# swimate.net
KiCad netlist of a schematic drawn in EAGLE
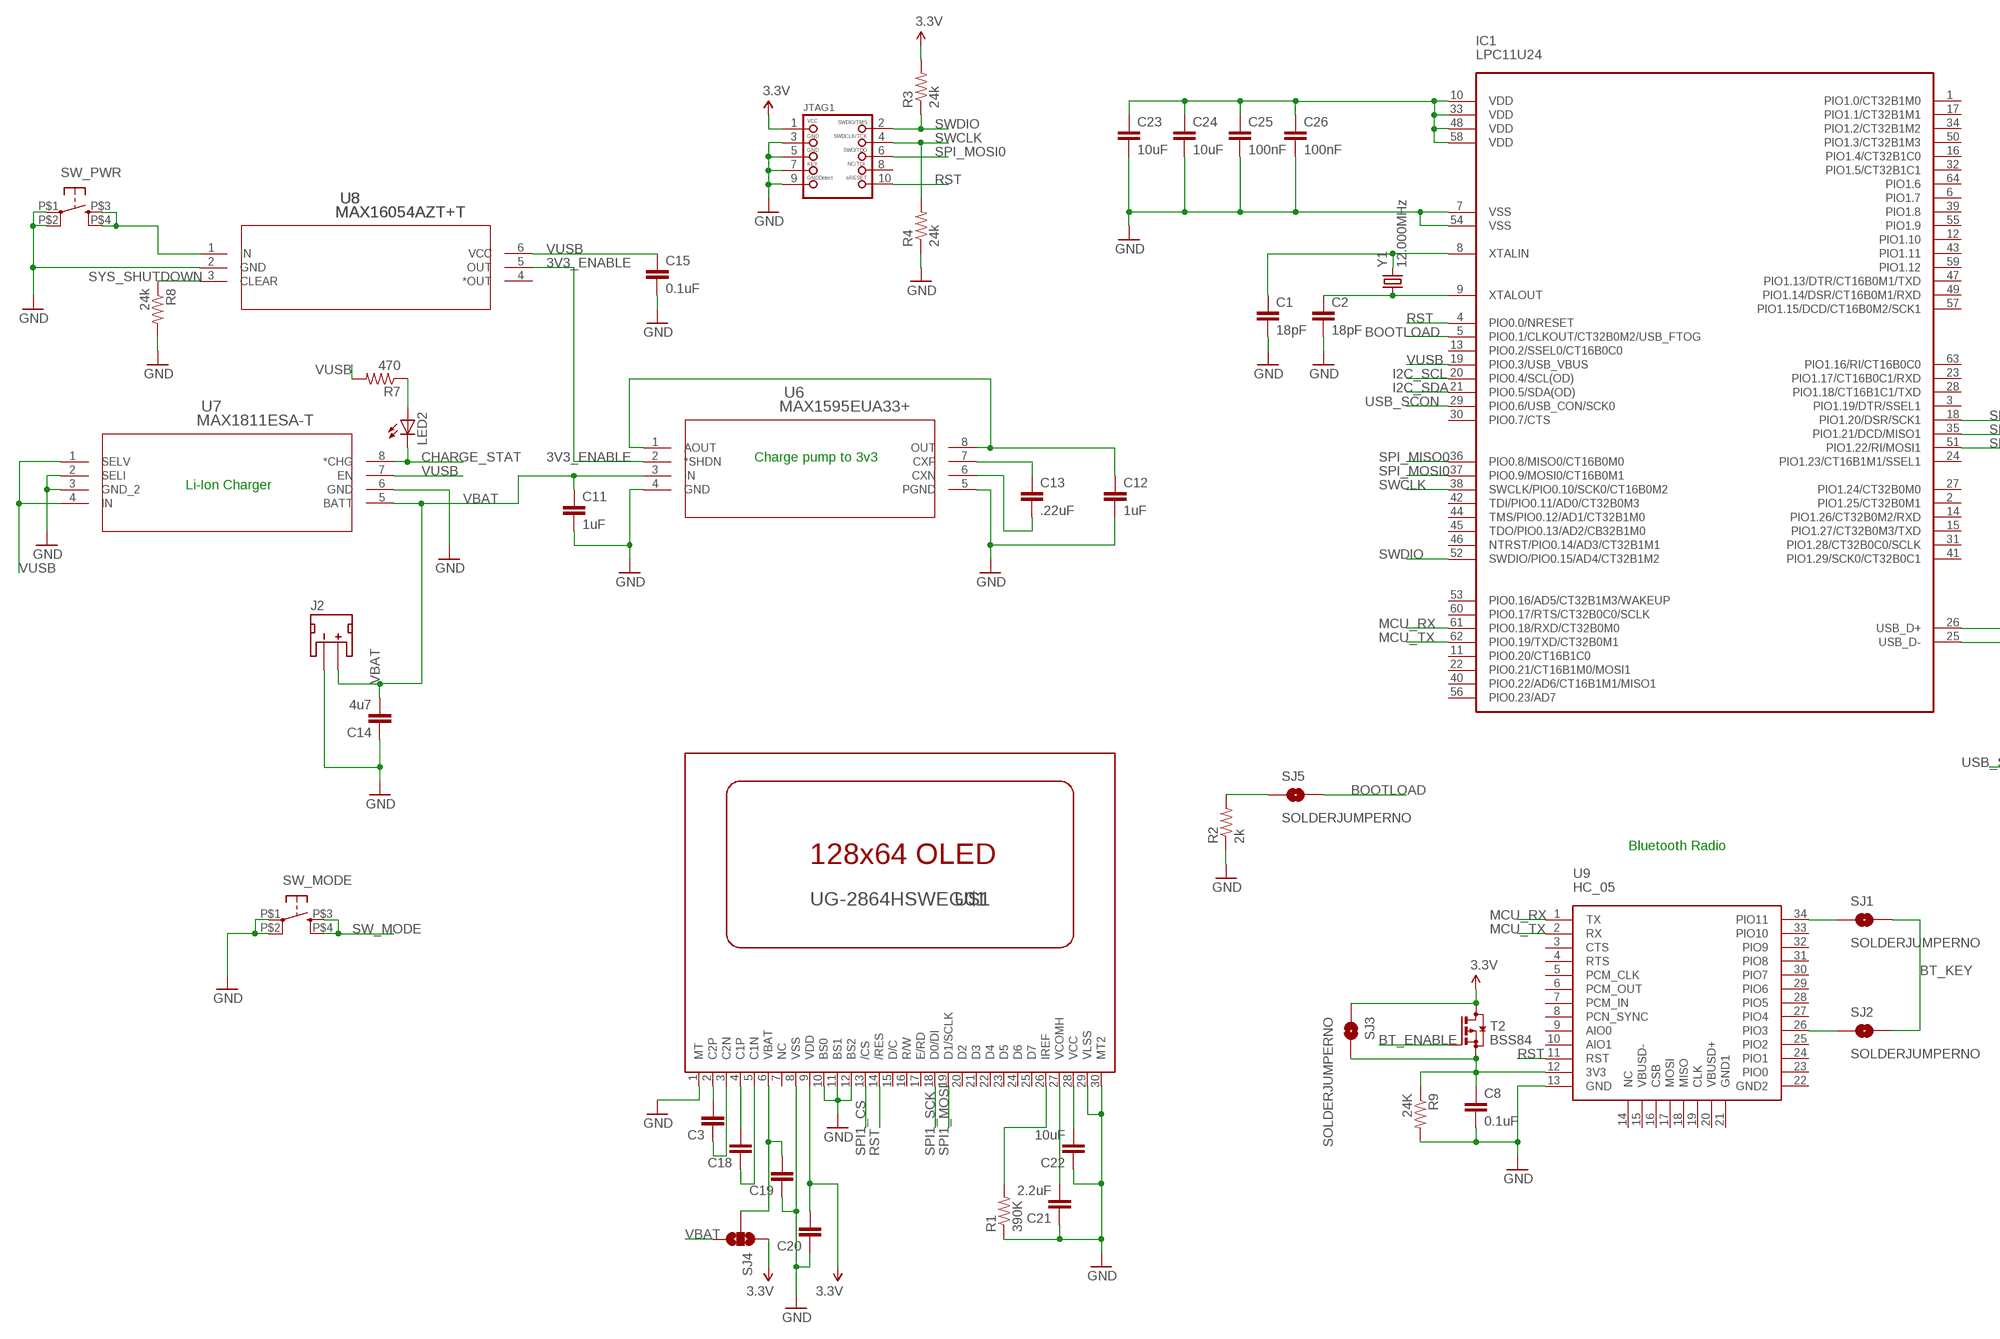
[diagram p0: schematic, sheet 1, part 1 of 2]
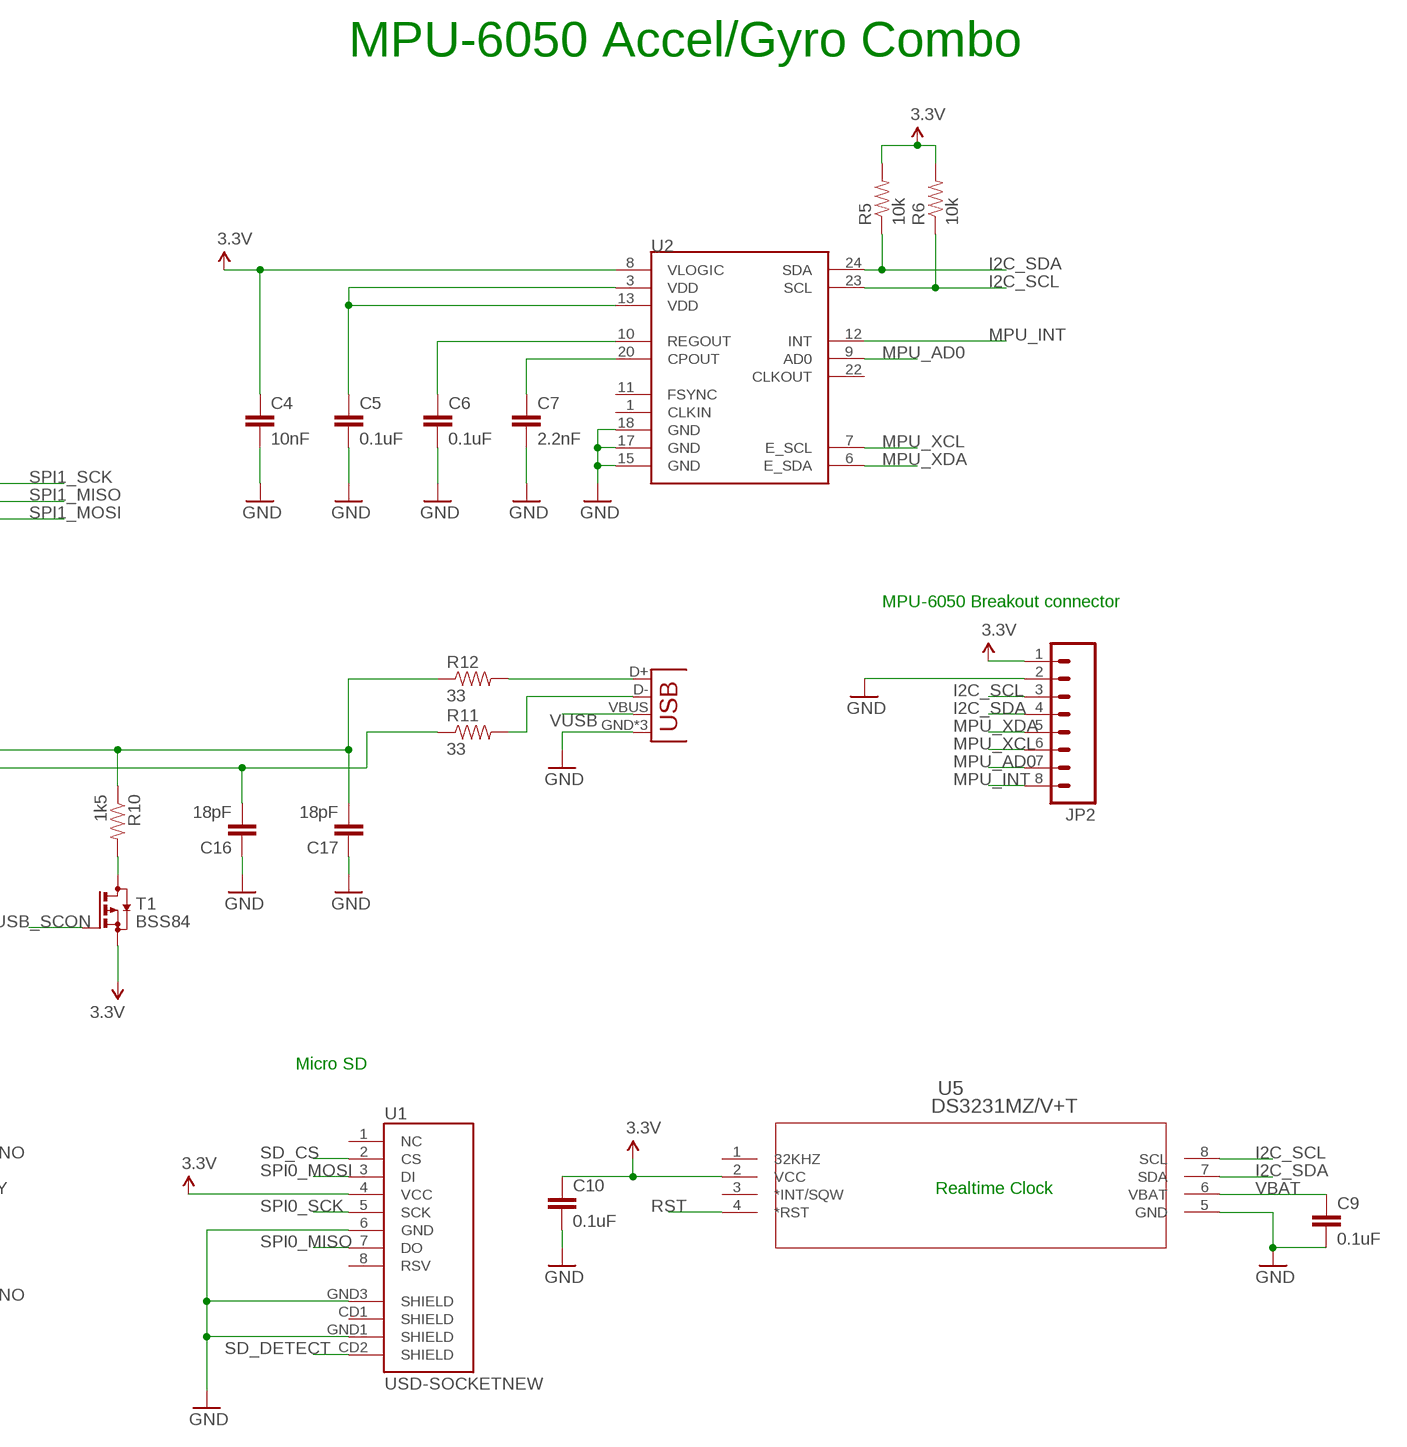
[diagram p1: schematic, sheet 1, part 2 of 2]

(export (version "E")
  (design (tool "Eeschema 10.0.6"))
  (components
    (comp (ref "C1")
      (value "18pF")
      (footprint "eagle-import:0805")
      (libsource (lib "eagle-import") (part "SparkFun-Passives_CAP0805"))
    )
    (comp (ref "C2")
      (value "18pF")
      (footprint "eagle-import:0805")
      (libsource (lib "eagle-import") (part "SparkFun-Passives_CAP0805"))
    )
    (comp (ref "C3")
      (value "CAP0805")
      (footprint "eagle-import:0805")
      (libsource (lib "eagle-import") (part "CAP0805"))
    )
    (comp (ref "C4")
      (value "10nF")
      (footprint "eagle-import:0805")
      (libsource (lib "eagle-import") (part "SparkFun-Passives_CAP0805"))
    )
    (comp (ref "C5")
      (value "0.1uF")
      (footprint "eagle-import:0805")
      (libsource (lib "eagle-import") (part "SparkFun-Passives_CAP0805"))
    )
    (comp (ref "C6")
      (value "0.1uF")
      (footprint "eagle-import:0805")
      (libsource (lib "eagle-import") (part "SparkFun-Passives_CAP0805"))
    )
    (comp (ref "C7")
      (value "2.2nF")
      (footprint "eagle-import:0805")
      (libsource (lib "eagle-import") (part "SparkFun-Passives_CAP0805"))
    )
    (comp (ref "C8")
      (value "0.1uF")
      (footprint "eagle-import:0805")
      (libsource (lib "eagle-import") (part "SparkFun-Passives_CAP0805"))
    )
    (comp (ref "C9")
      (value "0.1uF")
      (footprint "eagle-import:0805")
      (libsource (lib "eagle-import") (part "SparkFun-Passives_CAP0805"))
    )
    (comp (ref "C10")
      (value "0.1uF")
      (footprint "eagle-import:0805")
      (libsource (lib "eagle-import") (part "SparkFun-Passives_CAP0805"))
    )
    (comp (ref "C11")
      (value "1uF")
      (footprint "eagle-import:1206")
      (libsource (lib "eagle-import") (part "CAP1206"))
    )
    (comp (ref "C12")
      (value "1uF")
      (footprint "eagle-import:1206")
      (libsource (lib "eagle-import") (part "CAP1206"))
    )
    (comp (ref "C13")
      (value ".22uF")
      (footprint "eagle-import:0805")
      (libsource (lib "eagle-import") (part "SparkFun-Passives_CAP0805"))
    )
    (comp (ref "C14")
      (value "4u7")
      (footprint "eagle-import:1206")
      (libsource (lib "eagle-import") (part "SparkFun-Passives_CAP1206"))
    )
    (comp (ref "C15")
      (value "0.1uF")
      (footprint "eagle-import:0805")
      (libsource (lib "eagle-import") (part "SparkFun-Passives_CAP0805"))
    )
    (comp (ref "C16")
      (value "18pF")
      (footprint "eagle-import:0805")
      (libsource (lib "eagle-import") (part "SparkFun-Passives_CAP0805"))
    )
    (comp (ref "C17")
      (value "18pF")
      (footprint "eagle-import:0805")
      (libsource (lib "eagle-import") (part "SparkFun-Passives_CAP0805"))
    )
    (comp (ref "C18")
      (value "CAP0805")
      (footprint "eagle-import:0805")
      (libsource (lib "eagle-import") (part "CAP0805"))
    )
    (comp (ref "C19")
      (value "CAP0805")
      (footprint "eagle-import:0805")
      (libsource (lib "eagle-import") (part "CAP0805"))
    )
    (comp (ref "C20")
      (value "CAP0805")
      (footprint "eagle-import:0805")
      (libsource (lib "eagle-import") (part "CAP0805"))
    )
    (comp (ref "C21")
      (value "2.2uF")
      (footprint "eagle-import:0805")
      (libsource (lib "eagle-import") (part "CAP0805"))
    )
    (comp (ref "C22")
      (value "10uF")
      (footprint "eagle-import:0805")
      (libsource (lib "eagle-import") (part "CAP0805"))
    )
    (comp (ref "C23")
      (value "10uF")
      (footprint "eagle-import:0805")
      (libsource (lib "eagle-import") (part "CAP0805"))
    )
    (comp (ref "C24")
      (value "10uF")
      (footprint "eagle-import:0805")
      (libsource (lib "eagle-import") (part "CAP0805"))
    )
    (comp (ref "C25")
      (value "100nF")
      (footprint "eagle-import:0805")
      (libsource (lib "eagle-import") (part "CAP0805"))
    )
    (comp (ref "C26")
      (value "100nF")
      (footprint "eagle-import:0805")
      (libsource (lib "eagle-import") (part "CAP0805"))
    )
    (comp (ref "IC1")
      (value "LPC11U24")
      (footprint "eagle-import:MBED-ICS_LQFP64")
      (libsource (lib "eagle-import") (part "LPC11U24"))
    )
    (comp (ref "J2")
      (value "JST_2MM_MALE")
      (footprint "eagle-import:JST-2-SMD")
      (libsource (lib "eagle-import") (part "JST_2MM_MALE"))
    )
    (comp (ref "JP2")
      (value "M08")
      (footprint "eagle-import:1X08_PIN1_NO_SILK")
      (libsource (lib "eagle-import") (part "M08"))
    )
    (comp (ref "JP3")
      (value "USB-MICROB")
      (footprint "eagle-import:USB-MICROB")
      (libsource (lib "eagle-import") (part "USB-MICROB"))
    )
    (comp (ref "JTAG1")
      (value "JTAG-CORTEXM3")
      (footprint "eagle-import:2X05_1.27MM_SMT")
      (libsource (lib "eagle-import") (part "JTAG-CORTEXM3"))
    )
    (comp (ref "LED2")
      (value "LED1206")
      (footprint "eagle-import:LED-1206")
      (libsource (lib "eagle-import") (part "LED1206"))
    )
    (comp (ref "R1")
      (value "390K")
      (footprint "eagle-import:0805")
      (libsource (lib "eagle-import") (part "RESISTOR0805-RES"))
    )
    (comp (ref "R2")
      (value "2k")
      (footprint "eagle-import:0805")
      (libsource (lib "eagle-import") (part "RESISTOR0805-RES"))
    )
    (comp (ref "R3")
      (value "24k")
      (footprint "eagle-import:0805")
      (libsource (lib "eagle-import") (part "RESISTOR0805-RES"))
    )
    (comp (ref "R4")
      (value "24k")
      (footprint "eagle-import:0805")
      (libsource (lib "eagle-import") (part "RESISTOR0805-RES"))
    )
    (comp (ref "R5")
      (value "10k")
      (footprint "eagle-import:0805")
      (libsource (lib "eagle-import") (part "RESISTOR0805-RES"))
    )
    (comp (ref "R6")
      (value "10k")
      (footprint "eagle-import:0805")
      (libsource (lib "eagle-import") (part "RESISTOR0805-RES"))
    )
    (comp (ref "R7")
      (value "470")
      (footprint "eagle-import:0805")
      (libsource (lib "eagle-import") (part "RESISTOR0805-RES"))
    )
    (comp (ref "R8")
      (value "24k")
      (footprint "eagle-import:0805")
      (libsource (lib "eagle-import") (part "RESISTOR0805-RES"))
    )
    (comp (ref "R9")
      (value "24K")
      (footprint "eagle-import:0805")
      (libsource (lib "eagle-import") (part "RESISTOR0805-RES"))
    )
    (comp (ref "R10")
      (value "1k5")
      (footprint "eagle-import:0805")
      (libsource (lib "eagle-import") (part "RESISTOR0805-RES"))
    )
    (comp (ref "R11")
      (value "33")
      (footprint "eagle-import:0805")
      (libsource (lib "eagle-import") (part "RESISTOR0805-RES"))
    )
    (comp (ref "R12")
      (value "33")
      (footprint "eagle-import:0805")
      (libsource (lib "eagle-import") (part "RESISTOR0805-RES"))
    )
    (comp (ref "SJ1")
      (value "SOLDERJUMPERNO")
      (footprint "eagle-import:SJ_2S-NO")
      (libsource (lib "eagle-import") (part "SOLDERJUMPERNO"))
    )
    (comp (ref "SJ2")
      (value "SOLDERJUMPERNO")
      (footprint "eagle-import:SJ_2S-NO")
      (libsource (lib "eagle-import") (part "SOLDERJUMPERNO"))
    )
    (comp (ref "SJ3")
      (value "SOLDERJUMPERNO")
      (footprint "eagle-import:SJ_2S-NO")
      (libsource (lib "eagle-import") (part "SOLDERJUMPERNO"))
    )
    (comp (ref "SJ4")
      (value "SOLDERJUMPER_2WAYS")
      (footprint "eagle-import:SJ_3")
      (libsource (lib "eagle-import") (part "SOLDERJUMPER_2WAYS"))
    )
    (comp (ref "SJ5")
      (value "SOLDERJUMPERNO")
      (footprint "eagle-import:SJ_2S-NO")
      (libsource (lib "eagle-import") (part "SOLDERJUMPERNO"))
    )
    (comp (ref "SW_MODE")
      (value "TAC_SWITCHKSA_SEALED")
      (footprint "eagle-import:KSA_SEALED_TAC_SWITCH")
      (libsource (lib "eagle-import") (part "TAC_SWITCHKSA_SEALED"))
    )
    (comp (ref "SW_PWR")
      (value "TAC_SWITCHKSA_SEALED")
      (footprint "eagle-import:KSA_SEALED_TAC_SWITCH")
      (libsource (lib "eagle-import") (part "TAC_SWITCHKSA_SEALED"))
    )
    (comp (ref "T1")
      (value "BSS84")
      (footprint "eagle-import:SOT23")
      (libsource (lib "eagle-import") (part "BSS84"))
    )
    (comp (ref "T2")
      (value "BSS84")
      (footprint "eagle-import:SOT23")
      (libsource (lib "eagle-import") (part "BSS84"))
    )
    (comp (ref "U$1")
      (value "UG-2864HSWEG01")
      (footprint "eagle-import:1X30-0.7MM")
      (libsource (lib "eagle-import") (part "UG-2864HSWEG01"))
    )
    (comp (ref "U1")
      (value "USD-SOCKETNEW")
      (footprint "eagle-import:MICRO-SD-SOCKET-PP")
      (libsource (lib "eagle-import") (part "USD-SOCKETNEW"))
    )
    (comp (ref "U2")
      (value "MPU-9150QFN-24-NP")
      (footprint "eagle-import:QFN-24-NP")
      (libsource (lib "eagle-import") (part "MPU-9150QFN-24-NP"))
    )
    (comp (ref "U5")
      (value "DS3231MZ/V+T")
      (footprint "eagle-import:21-0041B_8")
      (libsource (lib "eagle-import") (part "DS3231MZ/V+T"))
    )
    (comp (ref "U6")
      (value "MAX1595EUA33+")
      (footprint "eagle-import:21-0036K")
      (libsource (lib "eagle-import") (part "MAX1595EUA33+"))
    )
    (comp (ref "U7")
      (value "MAX1811ESA-T")
      (footprint "eagle-import:21-0041B_8")
      (libsource (lib "eagle-import") (part "MAX1811ESA-T"))
    )
    (comp (ref "U8")
      (value "MAX16054AZT+T")
      (footprint "eagle-import:21-0114C")
      (libsource (lib "eagle-import") (part "MAX16054AZT+T"))
    )
    (comp (ref "U9")
      (value "HC_05")
      (footprint "eagle-import:BLUETOOTH_SMD")
      (libsource (lib "eagle-import") (part "HC_05"))
    )
    (comp (ref "Y1")
      (value "12.000MHz")
      (footprint "eagle-import:CRYSTAL-SMD-5X3")
      (libsource (lib "eagle-import") (part "CRYSTAL5X3"))
    )
  )
  (nets
    (net (code "1") (name "/3V3_ENABLE") (class "Default")
      (node (ref "U6") (pin "2") (pinfunction "*SHDN_2") (pintype "passive"))
      (node (ref "U8") (pin "5") (pinfunction "OUT_5") (pintype "output"))
    )
    (net (code "2") (name "/BOOTLOAD") (class "Default")
      (node (ref "IC1") (pin "5") (pinfunction "PIO0.1/CLKOUT/CT32B0M2/USB_FTOG_5") (pintype "bidirectional"))
      (node (ref "SJ5") (pin "2") (pinfunction "2_2") (pintype "passive"))
    )
    (net (code "3") (name "/BT_ENABLE") (class "Default")
      (node (ref "T2") (pin "1") (pinfunction "G_1") (pintype "passive"))
    )
    (net (code "4") (name "/BT_KEY") (class "Default")
      (node (ref "SJ1") (pin "2") (pinfunction "2_2") (pintype "passive"))
      (node (ref "SJ2") (pin "2") (pinfunction "2_2") (pintype "passive"))
    )
    (net (code "5") (name "/CHARGE_STAT") (class "Default")
      (node (ref "LED2") (pin "C") (pinfunction "C_C") (pintype "passive"))
      (node (ref "U7") (pin "8") (pinfunction "*CHG_8") (pintype "bidirectional"))
    )
    (net (code "6") (name "/I2C_SCL") (class "Default")
      (node (ref "IC1") (pin "20") (pinfunction "PIO0.4/SCL(OD)_20") (pintype "bidirectional"))
      (node (ref "JP2") (pin "3") (pinfunction "3_3") (pintype "passive"))
      (node (ref "R6") (pin "1") (pinfunction "1_1") (pintype "passive"))
      (node (ref "U2") (pin "23") (pinfunction "SCL_23") (pintype "bidirectional"))
      (node (ref "U5") (pin "8") (pinfunction "SCL_8") (pintype "passive"))
    )
    (net (code "7") (name "/I2C_SDA") (class "Default")
      (node (ref "IC1") (pin "21") (pinfunction "PIO0.5/SDA(OD)_21") (pintype "bidirectional"))
      (node (ref "JP2") (pin "4") (pinfunction "4_4") (pintype "passive"))
      (node (ref "R5") (pin "1") (pinfunction "1_1") (pintype "passive"))
      (node (ref "U2") (pin "24") (pinfunction "SDA_24") (pintype "bidirectional"))
      (node (ref "U5") (pin "7") (pinfunction "SDA_7") (pintype "passive"))
    )
    (net (code "8") (name "/MCU_RX") (class "Default")
      (node (ref "IC1") (pin "61") (pinfunction "PIO0.18/RXD/CT32B0M0_61") (pintype "bidirectional"))
      (node (ref "U9") (pin "1") (pinfunction "TX_1") (pintype "bidirectional"))
    )
    (net (code "9") (name "/MCU_TX") (class "Default")
      (node (ref "IC1") (pin "62") (pinfunction "PIO0.19/TXD/CT32B0M1_62") (pintype "bidirectional"))
      (node (ref "U9") (pin "2") (pinfunction "RX_2") (pintype "bidirectional"))
    )
    (net (code "10") (name "/MPU_AD0") (class "Default")
      (node (ref "JP2") (pin "7") (pinfunction "7_7") (pintype "passive"))
      (node (ref "U2") (pin "9") (pinfunction "AD0_9") (pintype "bidirectional"))
    )
    (net (code "11") (name "/MPU_INT") (class "Default")
      (node (ref "JP2") (pin "8") (pinfunction "8_8") (pintype "passive"))
      (node (ref "U2") (pin "12") (pinfunction "INT_12") (pintype "bidirectional"))
    )
    (net (code "12") (name "/MPU_XCL") (class "Default")
      (node (ref "JP2") (pin "6") (pinfunction "6_6") (pintype "passive"))
      (node (ref "U2") (pin "7") (pinfunction "E_SCL_7") (pintype "bidirectional"))
    )
    (net (code "13") (name "/MPU_XDA") (class "Default")
      (node (ref "JP2") (pin "5") (pinfunction "5_5") (pintype "passive"))
      (node (ref "U2") (pin "6") (pinfunction "E_SDA_6") (pintype "bidirectional"))
    )
    (net (code "14") (name "/RST") (class "Default")
      (node (ref "IC1") (pin "4") (pinfunction "PIO0.0/NRESET_4") (pintype "bidirectional"))
      (node (ref "JTAG1") (pin "10") (pinfunction "10_10") (pintype "passive"))
      (node (ref "U$1") (pin "14") (pinfunction "/RES_14") (pintype "input"))
      (node (ref "U5") (pin "4") (pinfunction "*RST_4") (pintype "passive"))
      (node (ref "U9") (pin "11") (pinfunction "RST_11") (pintype "bidirectional"))
    )
    (net (code "15") (name "/SD_CS") (class "Default")
      (node (ref "U1") (pin "2") (pinfunction "CS_2") (pintype "bidirectional"))
    )
    (net (code "16") (name "/SD_DETECT") (class "Default")
      (node (ref "U1") (pin "CD2") (pinfunction "SHIELD_CD2") (pintype "bidirectional"))
    )
    (net (code "17") (name "/SPI0_MISO") (class "Default")
      (node (ref "U1") (pin "7") (pinfunction "DO_7") (pintype "bidirectional"))
    )
    (net (code "18") (name "/SPI0_MOSI") (class "Default")
      (node (ref "U1") (pin "3") (pinfunction "DI_3") (pintype "bidirectional"))
    )
    (net (code "19") (name "/SPI0_SCK") (class "Default")
      (node (ref "U1") (pin "5") (pinfunction "SCK_5") (pintype "bidirectional"))
    )
    (net (code "20") (name "/SPI1_CS") (class "Default")
      (node (ref "U$1") (pin "13") (pinfunction "/CS_13") (pintype "input"))
    )
    (net (code "21") (name "/SPI1_MISO") (class "Default")
      (node (ref "IC1") (pin "35") (pinfunction "PIO1.21/DCD/MISO1_35") (pintype "bidirectional"))
    )
    (net (code "22") (name "/SPI1_MOSI") (class "Default")
      (node (ref "IC1") (pin "51") (pinfunction "PIO1.22/RI/MOSI1_51") (pintype "bidirectional"))
      (node (ref "U$1") (pin "19") (pinfunction "D1/SCLK_19") (pintype "bidirectional"))
    )
    (net (code "23") (name "/SPI1_SCK") (class "Default")
      (node (ref "IC1") (pin "18") (pinfunction "PIO1.20/DSR/SCK1_18") (pintype "bidirectional"))
      (node (ref "U$1") (pin "18") (pinfunction "D0/DI_18") (pintype "bidirectional"))
    )
    (net (code "24") (name "/SPI_MISO0") (class "Default")
      (node (ref "IC1") (pin "36") (pinfunction "PIO0.8/MISO0/CT16B0M0_36") (pintype "bidirectional"))
    )
    (net (code "25") (name "/SPI_MOSI0") (class "Default")
      (node (ref "IC1") (pin "37") (pinfunction "PIO0.9/MOSI0/CT16B0M1_37") (pintype "bidirectional"))
      (node (ref "JTAG1") (pin "6") (pinfunction "6_6") (pintype "passive"))
    )
    (net (code "26") (name "/SWCLK") (class "Default")
      (node (ref "IC1") (pin "38") (pinfunction "SWCLK/PIO0.10/SCK0/CT16B0M2_38") (pintype "bidirectional"))
      (node (ref "JTAG1") (pin "4") (pinfunction "4_4") (pintype "passive"))
      (node (ref "R4") (pin "2") (pinfunction "2_2") (pintype "passive"))
    )
    (net (code "27") (name "/SWDIO") (class "Default")
      (node (ref "IC1") (pin "52") (pinfunction "SWDIO/PIO0.15/AD4/CT32B1M2_52") (pintype "bidirectional"))
      (node (ref "JTAG1") (pin "2") (pinfunction "2_2") (pintype "passive"))
      (node (ref "R3") (pin "1") (pinfunction "1_1") (pintype "passive"))
    )
    (net (code "28") (name "/SW_MODE") (class "Default")
      (node (ref "SW_MODE") (pin "P$3") (pinfunction "3_P$3") (pintype "passive"))
      (node (ref "SW_MODE") (pin "P$4") (pinfunction "4_P$4") (pintype "passive"))
    )
    (net (code "29") (name "/SYS_SHUTDOWN") (class "Default")
      (node (ref "R8") (pin "1") (pinfunction "1_1") (pintype "passive"))
      (node (ref "U8") (pin "3") (pinfunction "CLEAR_3") (pintype "bidirectional"))
    )
    (net (code "30") (name "/USB_SCON") (class "Default")
      (node (ref "IC1") (pin "29") (pinfunction "PIO0.6/USB_CON/SCK0_29") (pintype "bidirectional"))
      (node (ref "T1") (pin "1") (pinfunction "G_1") (pintype "passive"))
    )
    (net (code "31") (name "/VBAT") (class "Default")
      (node (ref "C11") (pin "1") (pinfunction "1_1") (pintype "passive"))
      (node (ref "C14") (pin "2") (pinfunction "2_2") (pintype "passive"))
      (node (ref "C9") (pin "1") (pinfunction "1_1") (pintype "passive"))
      (node (ref "J2") (pin "2") (pinfunction "+_2") (pintype "bidirectional"))
      (node (ref "SJ4") (pin "3") (pinfunction "3_3") (pintype "passive"))
      (node (ref "U5") (pin "6") (pinfunction "VBAT_6") (pintype "power_in"))
      (node (ref "U6") (pin "3") (pinfunction "IN_3") (pintype "input"))
      (node (ref "U7") (pin "5") (pinfunction "BATT_5") (pintype "bidirectional"))
    )
    (net (code "32") (name "/VUSB") (class "Default")
      (node (ref "C15") (pin "1") (pinfunction "1_1") (pintype "passive"))
      (node (ref "IC1") (pin "19") (pinfunction "PIO0.3/USB_VBUS_19") (pintype "bidirectional"))
      (node (ref "JP3") (pin "VBUS") (pinfunction "VBUS_VBUS") (pintype "bidirectional"))
      (node (ref "R7") (pin "2") (pinfunction "2_2") (pintype "passive"))
      (node (ref "U7") (pin "1") (pinfunction "SELV_1") (pintype "bidirectional"))
      (node (ref "U7") (pin "4") (pinfunction "IN_4") (pintype "input"))
      (node (ref "U7") (pin "7") (pinfunction "EN_7") (pintype "bidirectional"))
      (node (ref "U8") (pin "6") (pinfunction "VCC_6") (pintype "power_in"))
    )
    (net (code "33") (name "3.3V") (class "Default")
      (node (ref "C10") (pin "1") (pinfunction "1_1") (pintype "passive"))
      (node (ref "C20") (pin "2") (pinfunction "2_2") (pintype "passive"))
      (node (ref "C4") (pin "1") (pinfunction "1_1") (pintype "passive"))
      (node (ref "JP2") (pin "1") (pinfunction "1_1") (pintype "passive"))
      (node (ref "JTAG1") (pin "1") (pinfunction "1_1") (pintype "passive"))
      (node (ref "R3") (pin "2") (pinfunction "2_2") (pintype "passive"))
      (node (ref "R5") (pin "2") (pinfunction "2_2") (pintype "passive"))
      (node (ref "R6") (pin "2") (pinfunction "2_2") (pintype "passive"))
      (node (ref "SJ3") (pin "1") (pinfunction "1_1") (pintype "passive"))
      (node (ref "SJ4") (pin "1") (pinfunction "1_1") (pintype "passive"))
      (node (ref "T1") (pin "2") (pinfunction "S_2") (pintype "passive"))
      (node (ref "T2") (pin "3") (pinfunction "D_3") (pintype "passive"))
      (node (ref "U$1") (pin "9") (pinfunction "VDD_9") (pintype "power_in"))
      (node (ref "U1") (pin "4") (pinfunction "VCC_4") (pintype "bidirectional"))
      (node (ref "U2") (pin "8") (pinfunction "VLOGIC_8") (pintype "bidirectional"))
      (node (ref "U5") (pin "2") (pinfunction "VCC_2") (pintype "power_in"))
    )
    (net (code "34") (name "GND") (class "Default")
      (node (ref "C1") (pin "2") (pinfunction "2_2") (pintype "passive"))
      (node (ref "C10") (pin "2") (pinfunction "2_2") (pintype "passive"))
      (node (ref "C11") (pin "2") (pinfunction "2_2") (pintype "passive"))
      (node (ref "C12") (pin "2") (pinfunction "2_2") (pintype "passive"))
      (node (ref "C14") (pin "1") (pinfunction "1_1") (pintype "passive"))
      (node (ref "C15") (pin "2") (pinfunction "2_2") (pintype "passive"))
      (node (ref "C16") (pin "1") (pinfunction "1_1") (pintype "passive"))
      (node (ref "C17") (pin "1") (pinfunction "1_1") (pintype "passive"))
      (node (ref "C19") (pin "1") (pinfunction "1_1") (pintype "passive"))
      (node (ref "C2") (pin "2") (pinfunction "2_2") (pintype "passive"))
      (node (ref "C20") (pin "1") (pinfunction "1_1") (pintype "passive"))
      (node (ref "C21") (pin "1") (pinfunction "1_1") (pintype "passive"))
      (node (ref "C22") (pin "1") (pinfunction "1_1") (pintype "passive"))
      (node (ref "C23") (pin "2") (pinfunction "2_2") (pintype "passive"))
      (node (ref "C24") (pin "2") (pinfunction "2_2") (pintype "passive"))
      (node (ref "C25") (pin "2") (pinfunction "2_2") (pintype "passive"))
      (node (ref "C26") (pin "2") (pinfunction "2_2") (pintype "passive"))
      (node (ref "C4") (pin "2") (pinfunction "2_2") (pintype "passive"))
      (node (ref "C5") (pin "2") (pinfunction "2_2") (pintype "passive"))
      (node (ref "C6") (pin "2") (pinfunction "2_2") (pintype "passive"))
      (node (ref "C7") (pin "2") (pinfunction "2_2") (pintype "passive"))
      (node (ref "C8") (pin "2") (pinfunction "2_2") (pintype "passive"))
      (node (ref "C9") (pin "2") (pinfunction "2_2") (pintype "passive"))
      (node (ref "IC1") (pin "54") (pinfunction "VSS_54") (pintype "bidirectional"))
      (node (ref "IC1") (pin "7") (pinfunction "VSS_7") (pintype "bidirectional"))
      (node (ref "J2") (pin "1") (pinfunction "-_1") (pintype "bidirectional"))
      (node (ref "JP2") (pin "2") (pinfunction "2_2") (pintype "passive"))
      (node (ref "JP3") (pin "GND") (pinfunction "GND_GND") (pintype "bidirectional"))
      (node (ref "JP3") (pin "MT1") (pinfunction "GND_MT1") (pintype "bidirectional"))
      (node (ref "JP3") (pin "MT2") (pinfunction "GND_MT2") (pintype "bidirectional"))
      (node (ref "JTAG1") (pin "3") (pinfunction "3_3") (pintype "passive"))
      (node (ref "JTAG1") (pin "5") (pinfunction "5_5") (pintype "passive"))
      (node (ref "JTAG1") (pin "7") (pinfunction "7_7") (pintype "passive"))
      (node (ref "JTAG1") (pin "9") (pinfunction "9_9") (pintype "passive"))
      (node (ref "R1") (pin "1") (pinfunction "1_1") (pintype "passive"))
      (node (ref "R2") (pin "1") (pinfunction "1_1") (pintype "passive"))
      (node (ref "R4") (pin "1") (pinfunction "1_1") (pintype "passive"))
      (node (ref "R8") (pin "2") (pinfunction "2_2") (pintype "passive"))
      (node (ref "R9") (pin "2") (pinfunction "2_2") (pintype "passive"))
      (node (ref "SW_MODE") (pin "P$1") (pinfunction "1_P$1") (pintype "passive"))
      (node (ref "SW_MODE") (pin "P$2") (pinfunction "2_P$2") (pintype "passive"))
      (node (ref "SW_PWR") (pin "P$1") (pinfunction "1_P$1") (pintype "passive"))
      (node (ref "SW_PWR") (pin "P$2") (pinfunction "2_P$2") (pintype "passive"))
      (node (ref "U$1") (pin "1") (pinfunction "MT_1") (pintype "input"))
      (node (ref "U$1") (pin "10") (pinfunction "BS0_10") (pintype "input"))
      (node (ref "U$1") (pin "11") (pinfunction "BS1_11") (pintype "input"))
      (node (ref "U$1") (pin "12") (pinfunction "BS2_12") (pintype "input"))
      (node (ref "U$1") (pin "29") (pinfunction "VLSS_29") (pintype "power_in"))
      (node (ref "U$1") (pin "30") (pinfunction "MT2_30") (pintype "input"))
      (node (ref "U$1") (pin "8") (pinfunction "VSS_8") (pintype "power_in"))
      (node (ref "U1") (pin "6") (pinfunction "GND_6") (pintype "bidirectional"))
      (node (ref "U1") (pin "GND1") (pinfunction "SHIELD_GND1") (pintype "bidirectional"))
      (node (ref "U1") (pin "GND3") (pinfunction "SHIELD_GND3") (pintype "bidirectional"))
      (node (ref "U2") (pin "15") (pinfunction "GND_15") (pintype "bidirectional"))
      (node (ref "U2") (pin "17") (pinfunction "GND_17") (pintype "bidirectional"))
      (node (ref "U2") (pin "18") (pinfunction "GND_18") (pintype "bidirectional"))
      (node (ref "U5") (pin "5") (pinfunction "GND_5") (pintype "power_in"))
      (node (ref "U6") (pin "4") (pinfunction "GND_4") (pintype "power_in"))
      (node (ref "U6") (pin "5") (pinfunction "PGND_5") (pintype "power_in"))
      (node (ref "U7") (pin "2") (pinfunction "SELI_2") (pintype "bidirectional"))
      (node (ref "U7") (pin "3") (pinfunction "GND_2_3") (pintype "power_in"))
      (node (ref "U7") (pin "6") (pinfunction "GND_6") (pintype "power_in"))
      (node (ref "U8") (pin "2") (pinfunction "GND_2") (pintype "power_in"))
      (node (ref "U9") (pin "13") (pinfunction "GND_13") (pintype "bidirectional"))
    )
    (net (code "35") (name "Net-(C5-Pad1)") (class "Default")
      (node (ref "C5") (pin "1") (pinfunction "1_1") (pintype "passive"))
      (node (ref "U2") (pin "13") (pinfunction "VDD_13") (pintype "bidirectional"))
      (node (ref "U2") (pin "3") (pinfunction "VDD_3") (pintype "bidirectional"))
    )
    (net (code "36") (name "Net-(C23-Pad1)") (class "Default")
      (node (ref "C23") (pin "1") (pinfunction "1_1") (pintype "passive"))
      (node (ref "C24") (pin "1") (pinfunction "1_1") (pintype "passive"))
      (node (ref "C25") (pin "1") (pinfunction "1_1") (pintype "passive"))
      (node (ref "C26") (pin "1") (pinfunction "1_1") (pintype "passive"))
      (node (ref "IC1") (pin "10") (pinfunction "VDD_10") (pintype "bidirectional"))
      (node (ref "IC1") (pin "33") (pinfunction "VDD_33") (pintype "bidirectional"))
      (node (ref "IC1") (pin "48") (pinfunction "VDD_48") (pintype "bidirectional"))
      (node (ref "IC1") (pin "58") (pinfunction "VDD_58") (pintype "bidirectional"))
    )
    (net (code "37") (name "Net-(IC1-USB_D+)") (class "Default")
      (node (ref "C17") (pin "2") (pinfunction "2_2") (pintype "passive"))
      (node (ref "IC1") (pin "26") (pinfunction "USB_D+_26") (pintype "bidirectional"))
      (node (ref "R10") (pin "1") (pinfunction "1_1") (pintype "passive"))
      (node (ref "R12") (pin "1") (pinfunction "1_1") (pintype "passive"))
    )
    (net (code "38") (name "Net-(IC1-USB_D-)") (class "Default")
      (node (ref "C16") (pin "2") (pinfunction "2_2") (pintype "passive"))
      (node (ref "IC1") (pin "25") (pinfunction "USB_D-_25") (pintype "bidirectional"))
      (node (ref "R11") (pin "1") (pinfunction "1_1") (pintype "passive"))
    )
    (net (code "39") (name "Net-(IC1-XTALIN)") (class "Default")
      (node (ref "C1") (pin "1") (pinfunction "1_1") (pintype "passive"))
      (node (ref "IC1") (pin "8") (pinfunction "XTALIN_8") (pintype "bidirectional"))
      (node (ref "Y1") (pin "3") (pinfunction "2_3") (pintype "passive"))
    )
    (net (code "40") (name "Net-(IC1-XTALOUT)") (class "Default")
      (node (ref "C2") (pin "1") (pinfunction "1_1") (pintype "passive"))
      (node (ref "IC1") (pin "9") (pinfunction "XTALOUT_9") (pintype "bidirectional"))
      (node (ref "Y1") (pin "1") (pinfunction "1_1") (pintype "passive"))
    )
    (net (code "41") (name "Net-(JP3-PadD+)") (class "Default")
      (node (ref "JP3") (pin "D+") (pinfunction "D+_D+") (pintype "bidirectional"))
      (node (ref "R12") (pin "2") (pinfunction "2_2") (pintype "passive"))
    )
    (net (code "42") (name "Net-(JP3-PadD-)") (class "Default")
      (node (ref "JP3") (pin "D-") (pinfunction "D-_D-") (pintype "bidirectional"))
      (node (ref "R11") (pin "2") (pinfunction "2_2") (pintype "passive"))
    )
    (net (code "43") (name "Net-(LED2-PadA)") (class "Default")
      (node (ref "LED2") (pin "A") (pinfunction "A_A") (pintype "passive"))
      (node (ref "R7") (pin "1") (pinfunction "1_1") (pintype "passive"))
    )
    (net (code "44") (name "Net-(R2-Pad2)") (class "Default")
      (node (ref "R2") (pin "2") (pinfunction "2_2") (pintype "passive"))
      (node (ref "SJ5") (pin "1") (pinfunction "1_1") (pintype "passive"))
    )
    (net (code "45") (name "Net-(SW_PWR-3)") (class "Default")
      (node (ref "SW_PWR") (pin "P$3") (pinfunction "3_P$3") (pintype "passive"))
      (node (ref "SW_PWR") (pin "P$4") (pinfunction "4_P$4") (pintype "passive"))
      (node (ref "U8") (pin "1") (pinfunction "IN_1") (pintype "input"))
    )
    (net (code "46") (name "Net-(T1-D)") (class "Default")
      (node (ref "R10") (pin "2") (pinfunction "2_2") (pintype "passive"))
      (node (ref "T1") (pin "3") (pinfunction "D_3") (pintype "passive"))
    )
    (net (code "47") (name "Net-(T2-S)") (class "Default")
      (node (ref "C8") (pin "1") (pinfunction "1_1") (pintype "passive"))
      (node (ref "R9") (pin "1") (pinfunction "1_1") (pintype "passive"))
      (node (ref "SJ3") (pin "2") (pinfunction "2_2") (pintype "passive"))
      (node (ref "T2") (pin "2") (pinfunction "S_2") (pintype "passive"))
      (node (ref "U9") (pin "12") (pinfunction "3V3_12") (pintype "bidirectional"))
    )
    (net (code "48") (name "Net-(U$1-C1N)") (class "Default")
      (node (ref "C18") (pin "1") (pinfunction "1_1") (pintype "passive"))
      (node (ref "U$1") (pin "5") (pinfunction "C1N_5") (pintype "input"))
    )
    (net (code "49") (name "Net-(U$1-C1P)") (class "Default")
      (node (ref "C18") (pin "2") (pinfunction "2_2") (pintype "passive"))
      (node (ref "U$1") (pin "4") (pinfunction "C1P_4") (pintype "input"))
    )
    (net (code "50") (name "Net-(U$1-C2N)") (class "Default")
      (node (ref "C3") (pin "1") (pinfunction "1_1") (pintype "passive"))
      (node (ref "U$1") (pin "3") (pinfunction "C2N_3") (pintype "input"))
    )
    (net (code "51") (name "Net-(U$1-C2P)") (class "Default")
      (node (ref "C3") (pin "2") (pinfunction "2_2") (pintype "passive"))
      (node (ref "U$1") (pin "2") (pinfunction "C2P_2") (pintype "input"))
    )
    (net (code "52") (name "Net-(U$1-IREF)") (class "Default")
      (node (ref "R1") (pin "2") (pinfunction "2_2") (pintype "passive"))
      (node (ref "U$1") (pin "26") (pinfunction "IREF_26") (pintype "input"))
    )
    (net (code "53") (name "Net-(U$1-VBAT)") (class "Default")
      (node (ref "C19") (pin "2") (pinfunction "2_2") (pintype "passive"))
      (node (ref "SJ4") (pin "2") (pinfunction "2_2") (pintype "passive"))
      (node (ref "U$1") (pin "6") (pinfunction "VBAT_6") (pintype "input"))
    )
    (net (code "54") (name "Net-(U$1-VCC)") (class "Default")
      (node (ref "C22") (pin "2") (pinfunction "2_2") (pintype "passive"))
      (node (ref "U$1") (pin "28") (pinfunction "VCC_28") (pintype "power_in"))
    )
    (net (code "55") (name "Net-(U$1-VCOMH)") (class "Default")
      (node (ref "C21") (pin "2") (pinfunction "2_2") (pintype "passive"))
      (node (ref "U$1") (pin "27") (pinfunction "VCOMH_27") (pintype "output"))
    )
    (net (code "56") (name "Net-(U2-CPOUT)") (class "Default")
      (node (ref "C7") (pin "1") (pinfunction "1_1") (pintype "passive"))
      (node (ref "U2") (pin "20") (pinfunction "CPOUT_20") (pintype "bidirectional"))
    )
    (net (code "57") (name "Net-(U2-REGOUT)") (class "Default")
      (node (ref "C6") (pin "1") (pinfunction "1_1") (pintype "passive"))
      (node (ref "U2") (pin "10") (pinfunction "REGOUT_10") (pintype "bidirectional"))
    )
    (net (code "58") (name "Net-(U6-AOUT)") (class "Default")
      (node (ref "C12") (pin "1") (pinfunction "1_1") (pintype "passive"))
      (node (ref "U6") (pin "1") (pinfunction "AOUT_1") (pintype "output"))
      (node (ref "U6") (pin "8") (pinfunction "OUT_8") (pintype "output"))
    )
    (net (code "59") (name "Net-(U6-CXN)") (class "Default")
      (node (ref "C13") (pin "2") (pinfunction "2_2") (pintype "passive"))
      (node (ref "U6") (pin "6") (pinfunction "CXN_6") (pintype "passive"))
    )
    (net (code "60") (name "Net-(U6-CXP)") (class "Default")
      (node (ref "C13") (pin "1") (pinfunction "1_1") (pintype "passive"))
      (node (ref "U6") (pin "7") (pinfunction "CXP_7") (pintype "passive"))
    )
    (net (code "61") (name "Net-(U9-PIO3)") (class "Default")
      (node (ref "SJ2") (pin "1") (pinfunction "1_1") (pintype "passive"))
      (node (ref "U9") (pin "26") (pinfunction "PIO3_26") (pintype "bidirectional"))
    )
    (net (code "62") (name "Net-(U9-PIO11)") (class "Default")
      (node (ref "SJ1") (pin "1") (pinfunction "1_1") (pintype "passive"))
      (node (ref "U9") (pin "34") (pinfunction "PIO11_34") (pintype "bidirectional"))
    )
    (net (code "63") (name "unconnected-(IC1-NTRST{slash}PIO0.14{slash}AD3{slash}CT32B1M1-Pad46)") (class "Default")
      (node (ref "IC1") (pin "46") (pinfunction "NTRST/PIO0.14/AD3/CT32B1M1_46") (pintype "bidirectional"))
    )
    (net (code "64") (name "unconnected-(IC1-PIO0.2{slash}SSEL0{slash}CT16B0C0-Pad13)") (class "Default")
      (node (ref "IC1") (pin "13") (pinfunction "PIO0.2/SSEL0/CT16B0C0_13") (pintype "bidirectional"))
    )
    (net (code "65") (name "unconnected-(IC1-PIO0.7{slash}CTS-Pad30)") (class "Default")
      (node (ref "IC1") (pin "30") (pinfunction "PIO0.7/CTS_30") (pintype "bidirectional"))
    )
    (net (code "66") (name "unconnected-(IC1-PIO0.16{slash}AD5{slash}CT32B1M3{slash}WAKEUP-Pad53)") (class "Default")
      (node (ref "IC1") (pin "53") (pinfunction "PIO0.16/AD5/CT32B1M3/WAKEUP_53") (pintype "bidirectional"))
    )
    (net (code "67") (name "unconnected-(IC1-PIO0.17{slash}RTS{slash}CT32B0C0{slash}SCLK-Pad60)") (class "Default")
      (node (ref "IC1") (pin "60") (pinfunction "PIO0.17/RTS/CT32B0C0/SCLK_60") (pintype "bidirectional"))
    )
    (net (code "68") (name "unconnected-(IC1-PIO0.20{slash}CT16B1C0-Pad11)") (class "Default")
      (node (ref "IC1") (pin "11") (pinfunction "PIO0.20/CT16B1C0_11") (pintype "bidirectional"))
    )
    (net (code "69") (name "unconnected-(IC1-PIO0.21{slash}CT16B1M0{slash}MOSI1-Pad22)") (class "Default")
      (node (ref "IC1") (pin "22") (pinfunction "PIO0.21/CT16B1M0/MOSI1_22") (pintype "bidirectional"))
    )
    (net (code "70") (name "unconnected-(IC1-PIO0.22{slash}AD6{slash}CT16B1M1{slash}MISO1-Pad40)") (class "Default")
      (node (ref "IC1") (pin "40") (pinfunction "PIO0.22/AD6/CT16B1M1/MISO1_40") (pintype "bidirectional"))
    )
    (net (code "71") (name "unconnected-(IC1-PIO0.23{slash}AD7-Pad56)") (class "Default")
      (node (ref "IC1") (pin "56") (pinfunction "PIO0.23/AD7_56") (pintype "bidirectional"))
    )
    (net (code "72") (name "unconnected-(IC1-PIO1.0{slash}CT32B1M0-Pad1)") (class "Default")
      (node (ref "IC1") (pin "1") (pinfunction "PIO1.0/CT32B1M0_1") (pintype "bidirectional"))
    )
    (net (code "73") (name "unconnected-(IC1-PIO1.1{slash}CT32B1M1-Pad17)") (class "Default")
      (node (ref "IC1") (pin "17") (pinfunction "PIO1.1/CT32B1M1_17") (pintype "bidirectional"))
    )
    (net (code "74") (name "unconnected-(IC1-PIO1.2{slash}CT32B1M2-Pad34)") (class "Default")
      (node (ref "IC1") (pin "34") (pinfunction "PIO1.2/CT32B1M2_34") (pintype "bidirectional"))
    )
    (net (code "75") (name "unconnected-(IC1-PIO1.3{slash}CT32B1M3-Pad50)") (class "Default")
      (node (ref "IC1") (pin "50") (pinfunction "PIO1.3/CT32B1M3_50") (pintype "bidirectional"))
    )
    (net (code "76") (name "unconnected-(IC1-PIO1.4{slash}CT32B1C0-Pad16)") (class "Default")
      (node (ref "IC1") (pin "16") (pinfunction "PIO1.4/CT32B1C0_16") (pintype "bidirectional"))
    )
    (net (code "77") (name "unconnected-(IC1-PIO1.5{slash}CT32B1C1-Pad32)") (class "Default")
      (node (ref "IC1") (pin "32") (pinfunction "PIO1.5/CT32B1C1_32") (pintype "bidirectional"))
    )
    (net (code "78") (name "unconnected-(IC1-PIO1.6-Pad64)") (class "Default")
      (node (ref "IC1") (pin "64") (pinfunction "PIO1.6_64") (pintype "bidirectional"))
    )
    (net (code "79") (name "unconnected-(IC1-PIO1.7-Pad6)") (class "Default")
      (node (ref "IC1") (pin "6") (pinfunction "PIO1.7_6") (pintype "bidirectional"))
    )
    (net (code "80") (name "unconnected-(IC1-PIO1.8-Pad39)") (class "Default")
      (node (ref "IC1") (pin "39") (pinfunction "PIO1.8_39") (pintype "bidirectional"))
    )
    (net (code "81") (name "unconnected-(IC1-PIO1.9-Pad55)") (class "Default")
      (node (ref "IC1") (pin "55") (pinfunction "PIO1.9_55") (pintype "bidirectional"))
    )
    (net (code "82") (name "unconnected-(IC1-PIO1.10-Pad12)") (class "Default")
      (node (ref "IC1") (pin "12") (pinfunction "PIO1.10_12") (pintype "bidirectional"))
    )
    (net (code "83") (name "unconnected-(IC1-PIO1.11-Pad43)") (class "Default")
      (node (ref "IC1") (pin "43") (pinfunction "PIO1.11_43") (pintype "bidirectional"))
    )
    (net (code "84") (name "unconnected-(IC1-PIO1.12-Pad59)") (class "Default")
      (node (ref "IC1") (pin "59") (pinfunction "PIO1.12_59") (pintype "bidirectional"))
    )
    (net (code "85") (name "unconnected-(IC1-PIO1.13{slash}DTR{slash}CT16B0M1{slash}TXD-Pad47)") (class "Default")
      (node (ref "IC1") (pin "47") (pinfunction "PIO1.13/DTR/CT16B0M1/TXD_47") (pintype "bidirectional"))
    )
    (net (code "86") (name "unconnected-(IC1-PIO1.14{slash}DSR{slash}CT16B0M1{slash}RXD-Pad49)") (class "Default")
      (node (ref "IC1") (pin "49") (pinfunction "PIO1.14/DSR/CT16B0M1/RXD_49") (pintype "bidirectional"))
    )
    (net (code "87") (name "unconnected-(IC1-PIO1.15{slash}DCD{slash}CT16B0M2{slash}SCK1-Pad57)") (class "Default")
      (node (ref "IC1") (pin "57") (pinfunction "PIO1.15/DCD/CT16B0M2/SCK1_57") (pintype "bidirectional"))
    )
    (net (code "88") (name "unconnected-(IC1-PIO1.16{slash}RI{slash}CT16B0C0-Pad63)") (class "Default")
      (node (ref "IC1") (pin "63") (pinfunction "PIO1.16/RI/CT16B0C0_63") (pintype "bidirectional"))
    )
    (net (code "89") (name "unconnected-(IC1-PIO1.17{slash}CT16B0C1{slash}RXD-Pad23)") (class "Default")
      (node (ref "IC1") (pin "23") (pinfunction "PIO1.17/CT16B0C1/RXD_23") (pintype "bidirectional"))
    )
    (net (code "90") (name "unconnected-(IC1-PIO1.18{slash}CT16B1C1{slash}TXD-Pad28)") (class "Default")
      (node (ref "IC1") (pin "28") (pinfunction "PIO1.18/CT16B1C1/TXD_28") (pintype "bidirectional"))
    )
    (net (code "91") (name "unconnected-(IC1-PIO1.19{slash}DTR{slash}SSEL1-Pad3)") (class "Default")
      (node (ref "IC1") (pin "3") (pinfunction "PIO1.19/DTR/SSEL1_3") (pintype "bidirectional"))
    )
    (net (code "92") (name "unconnected-(IC1-PIO1.23{slash}CT16B1M1{slash}SSEL1-Pad24)") (class "Default")
      (node (ref "IC1") (pin "24") (pinfunction "PIO1.23/CT16B1M1/SSEL1_24") (pintype "bidirectional"))
    )
    (net (code "93") (name "unconnected-(IC1-PIO1.24{slash}CT32B0M0-Pad27)") (class "Default")
      (node (ref "IC1") (pin "27") (pinfunction "PIO1.24/CT32B0M0_27") (pintype "bidirectional"))
    )
    (net (code "94") (name "unconnected-(IC1-PIO1.25{slash}CT32B0M1-Pad2)") (class "Default")
      (node (ref "IC1") (pin "2") (pinfunction "PIO1.25/CT32B0M1_2") (pintype "bidirectional"))
    )
    (net (code "95") (name "unconnected-(IC1-PIO1.26{slash}CT32B0M2{slash}RXD-Pad14)") (class "Default")
      (node (ref "IC1") (pin "14") (pinfunction "PIO1.26/CT32B0M2/RXD_14") (pintype "bidirectional"))
    )
    (net (code "96") (name "unconnected-(IC1-PIO1.27{slash}CT32B0M3{slash}TXD-Pad15)") (class "Default")
      (node (ref "IC1") (pin "15") (pinfunction "PIO1.27/CT32B0M3/TXD_15") (pintype "bidirectional"))
    )
    (net (code "97") (name "unconnected-(IC1-PIO1.28{slash}CT32B0C0{slash}SCLK-Pad31)") (class "Default")
      (node (ref "IC1") (pin "31") (pinfunction "PIO1.28/CT32B0C0/SCLK_31") (pintype "bidirectional"))
    )
    (net (code "98") (name "unconnected-(IC1-PIO1.29{slash}SCK0{slash}CT32B0C1-Pad41)") (class "Default")
      (node (ref "IC1") (pin "41") (pinfunction "PIO1.29/SCK0/CT32B0C1_41") (pintype "bidirectional"))
    )
    (net (code "99") (name "unconnected-(IC1-TDI{slash}PIO0.11{slash}AD0{slash}CT32B0M3-Pad42)") (class "Default")
      (node (ref "IC1") (pin "42") (pinfunction "TDI/PIO0.11/AD0/CT32B0M3_42") (pintype "bidirectional"))
    )
    (net (code "100") (name "unconnected-(IC1-TDO{slash}PIO0.13{slash}AD2{slash}CB32B1M0-Pad45)") (class "Default")
      (node (ref "IC1") (pin "45") (pinfunction "TDO/PIO0.13/AD2/CB32B1M0_45") (pintype "bidirectional"))
    )
    (net (code "101") (name "unconnected-(IC1-TMS{slash}PIO0.12{slash}AD1{slash}CT32B1M0-Pad44)") (class "Default")
      (node (ref "IC1") (pin "44") (pinfunction "TMS/PIO0.12/AD1/CT32B1M0_44") (pintype "bidirectional"))
    )
    (net (code "102") (name "unconnected-(J2-PAD1-PadNC1)") (class "Default")
      (node (ref "J2") (pin "NC1") (pinfunction "PAD1_NC1") (pintype "bidirectional"))
    )
    (net (code "103") (name "unconnected-(J2-PAD2-PadNC2)") (class "Default")
      (node (ref "J2") (pin "NC2") (pinfunction "PAD2_NC2") (pintype "bidirectional"))
    )
    (net (code "104") (name "unconnected-(JTAG1-Pad8)") (class "Default")
      (node (ref "JTAG1") (pin "8") (pinfunction "8_8") (pintype "passive"))
    )
    (net (code "105") (name "unconnected-(U$1-D2-Pad20)") (class "Default")
      (node (ref "U$1") (pin "20") (pinfunction "D2_20") (pintype "bidirectional"))
    )
    (net (code "106") (name "unconnected-(U$1-D3-Pad21)") (class "Default")
      (node (ref "U$1") (pin "21") (pinfunction "D3_21") (pintype "bidirectional"))
    )
    (net (code "107") (name "unconnected-(U$1-D4-Pad22)") (class "Default")
      (node (ref "U$1") (pin "22") (pinfunction "D4_22") (pintype "bidirectional"))
    )
    (net (code "108") (name "unconnected-(U$1-D5-Pad23)") (class "Default")
      (node (ref "U$1") (pin "23") (pinfunction "D5_23") (pintype "bidirectional"))
    )
    (net (code "109") (name "unconnected-(U$1-D6-Pad24)") (class "Default")
      (node (ref "U$1") (pin "24") (pinfunction "D6_24") (pintype "bidirectional"))
    )
    (net (code "110") (name "unconnected-(U$1-D7-Pad25)") (class "Default")
      (node (ref "U$1") (pin "25") (pinfunction "D7_25") (pintype "bidirectional"))
    )
    (net (code "111") (name "unconnected-(U$1-D{slash}C-Pad15)") (class "Default")
      (node (ref "U$1") (pin "15") (pinfunction "D/C_15") (pintype "input"))
    )
    (net (code "112") (name "unconnected-(U$1-E{slash}RD-Pad17)") (class "Default")
      (node (ref "U$1") (pin "17") (pinfunction "E/RD_17") (pintype "input"))
    )
    (net (code "113") (name "unconnected-(U$1-NC-Pad7)") (class "Default")
      (node (ref "U$1") (pin "7") (pinfunction "NC_7") (pintype "no_connect"))
    )
    (net (code "114") (name "unconnected-(U$1-R{slash}W-Pad16)") (class "Default")
      (node (ref "U$1") (pin "16") (pinfunction "R/W_16") (pintype "input"))
    )
    (net (code "115") (name "unconnected-(U1-NC-Pad1)") (class "Default")
      (node (ref "U1") (pin "1") (pinfunction "NC_1") (pintype "bidirectional"))
    )
    (net (code "116") (name "unconnected-(U1-RSV-Pad8)") (class "Default")
      (node (ref "U1") (pin "8") (pinfunction "RSV_8") (pintype "bidirectional"))
    )
    (net (code "117") (name "unconnected-(U1-SHIELD-PadCD1)") (class "Default")
      (node (ref "U1") (pin "CD1") (pinfunction "SHIELD_CD1") (pintype "bidirectional"))
    )
    (net (code "118") (name "unconnected-(U2-CLKIN-Pad1)") (class "Default")
      (node (ref "U2") (pin "1") (pinfunction "CLKIN_1") (pintype "bidirectional"))
    )
    (net (code "119") (name "unconnected-(U2-CLKOUT-Pad22)") (class "Default")
      (node (ref "U2") (pin "22") (pinfunction "CLKOUT_22") (pintype "bidirectional"))
    )
    (net (code "120") (name "unconnected-(U2-FSYNC-Pad11)") (class "Default")
      (node (ref "U2") (pin "11") (pinfunction "FSYNC_11") (pintype "bidirectional"))
    )
    (net (code "121") (name "unconnected-(U5-*INT{slash}SQW-Pad3)") (class "Default")
      (node (ref "U5") (pin "3") (pinfunction "*INT/SQW_3") (pintype "passive"))
    )
    (net (code "122") (name "unconnected-(U5-32KHZ-Pad1)") (class "Default")
      (node (ref "U5") (pin "1") (pinfunction "32KHZ_1") (pintype "passive"))
    )
    (net (code "123") (name "unconnected-(U8-*OUT-Pad4)") (class "Default")
      (node (ref "U8") (pin "4") (pinfunction "*OUT_4") (pintype "output"))
    )
    (net (code "124") (name "unconnected-(U9-AIO0-Pad9)") (class "Default")
      (node (ref "U9") (pin "9") (pinfunction "AIO0_9") (pintype "bidirectional"))
    )
    (net (code "125") (name "unconnected-(U9-AIO1-Pad10)") (class "Default")
      (node (ref "U9") (pin "10") (pinfunction "AIO1_10") (pintype "bidirectional"))
    )
    (net (code "126") (name "unconnected-(U9-CLK-Pad19)") (class "Default")
      (node (ref "U9") (pin "19") (pinfunction "CLK_19") (pintype "bidirectional"))
    )
    (net (code "127") (name "unconnected-(U9-CSB-Pad16)") (class "Default")
      (node (ref "U9") (pin "16") (pinfunction "CSB_16") (pintype "bidirectional"))
    )
    (net (code "128") (name "unconnected-(U9-CTS-Pad3)") (class "Default")
      (node (ref "U9") (pin "3") (pinfunction "CTS_3") (pintype "bidirectional"))
    )
    (net (code "129") (name "unconnected-(U9-GND1-Pad21)") (class "Default")
      (node (ref "U9") (pin "21") (pinfunction "GND1_21") (pintype "bidirectional"))
    )
    (net (code "130") (name "unconnected-(U9-GND2-Pad22)") (class "Default")
      (node (ref "U9") (pin "22") (pinfunction "GND2_22") (pintype "bidirectional"))
    )
    (net (code "131") (name "unconnected-(U9-MISO-Pad18)") (class "Default")
      (node (ref "U9") (pin "18") (pinfunction "MISO_18") (pintype "bidirectional"))
    )
    (net (code "132") (name "unconnected-(U9-MOSI-Pad17)") (class "Default")
      (node (ref "U9") (pin "17") (pinfunction "MOSI_17") (pintype "bidirectional"))
    )
    (net (code "133") (name "unconnected-(U9-NC-Pad14)") (class "Default")
      (node (ref "U9") (pin "14") (pinfunction "NC_14") (pintype "bidirectional"))
    )
    (net (code "134") (name "unconnected-(U9-PCM_CLK-Pad5)") (class "Default")
      (node (ref "U9") (pin "5") (pinfunction "PCM_CLK_5") (pintype "bidirectional"))
    )
    (net (code "135") (name "unconnected-(U9-PCM_IN-Pad7)") (class "Default")
      (node (ref "U9") (pin "7") (pinfunction "PCM_IN_7") (pintype "bidirectional"))
    )
    (net (code "136") (name "unconnected-(U9-PCM_OUT-Pad6)") (class "Default")
      (node (ref "U9") (pin "6") (pinfunction "PCM_OUT_6") (pintype "bidirectional"))
    )
    (net (code "137") (name "unconnected-(U9-PCN_SYNC-Pad8)") (class "Default")
      (node (ref "U9") (pin "8") (pinfunction "PCN_SYNC_8") (pintype "bidirectional"))
    )
    (net (code "138") (name "unconnected-(U9-PIO0-Pad23)") (class "Default")
      (node (ref "U9") (pin "23") (pinfunction "PIO0_23") (pintype "bidirectional"))
    )
    (net (code "139") (name "unconnected-(U9-PIO1-Pad24)") (class "Default")
      (node (ref "U9") (pin "24") (pinfunction "PIO1_24") (pintype "bidirectional"))
    )
    (net (code "140") (name "unconnected-(U9-PIO2-Pad25)") (class "Default")
      (node (ref "U9") (pin "25") (pinfunction "PIO2_25") (pintype "bidirectional"))
    )
    (net (code "141") (name "unconnected-(U9-PIO4-Pad27)") (class "Default")
      (node (ref "U9") (pin "27") (pinfunction "PIO4_27") (pintype "bidirectional"))
    )
    (net (code "142") (name "unconnected-(U9-PIO5-Pad28)") (class "Default")
      (node (ref "U9") (pin "28") (pinfunction "PIO5_28") (pintype "bidirectional"))
    )
    (net (code "143") (name "unconnected-(U9-PIO6-Pad29)") (class "Default")
      (node (ref "U9") (pin "29") (pinfunction "PIO6_29") (pintype "bidirectional"))
    )
    (net (code "144") (name "unconnected-(U9-PIO7-Pad30)") (class "Default")
      (node (ref "U9") (pin "30") (pinfunction "PIO7_30") (pintype "bidirectional"))
    )
    (net (code "145") (name "unconnected-(U9-PIO8-Pad31)") (class "Default")
      (node (ref "U9") (pin "31") (pinfunction "PIO8_31") (pintype "bidirectional"))
    )
    (net (code "146") (name "unconnected-(U9-PIO9-Pad32)") (class "Default")
      (node (ref "U9") (pin "32") (pinfunction "PIO9_32") (pintype "bidirectional"))
    )
    (net (code "147") (name "unconnected-(U9-PIO10-Pad33)") (class "Default")
      (node (ref "U9") (pin "33") (pinfunction "PIO10_33") (pintype "bidirectional"))
    )
    (net (code "148") (name "unconnected-(U9-RTS-Pad4)") (class "Default")
      (node (ref "U9") (pin "4") (pinfunction "RTS_4") (pintype "bidirectional"))
    )
    (net (code "149") (name "unconnected-(U9-VBUSD+-Pad20)") (class "Default")
      (node (ref "U9") (pin "20") (pinfunction "VBUSD+_20") (pintype "bidirectional"))
    )
    (net (code "150") (name "unconnected-(U9-VBUSD--Pad15)") (class "Default")
      (node (ref "U9") (pin "15") (pinfunction "VBUSD-_15") (pintype "bidirectional"))
    )
  )
)
